# RADC-Microcontroller-S02-V00.net
KiCad netlist of a schematic drawn in Altium Designer
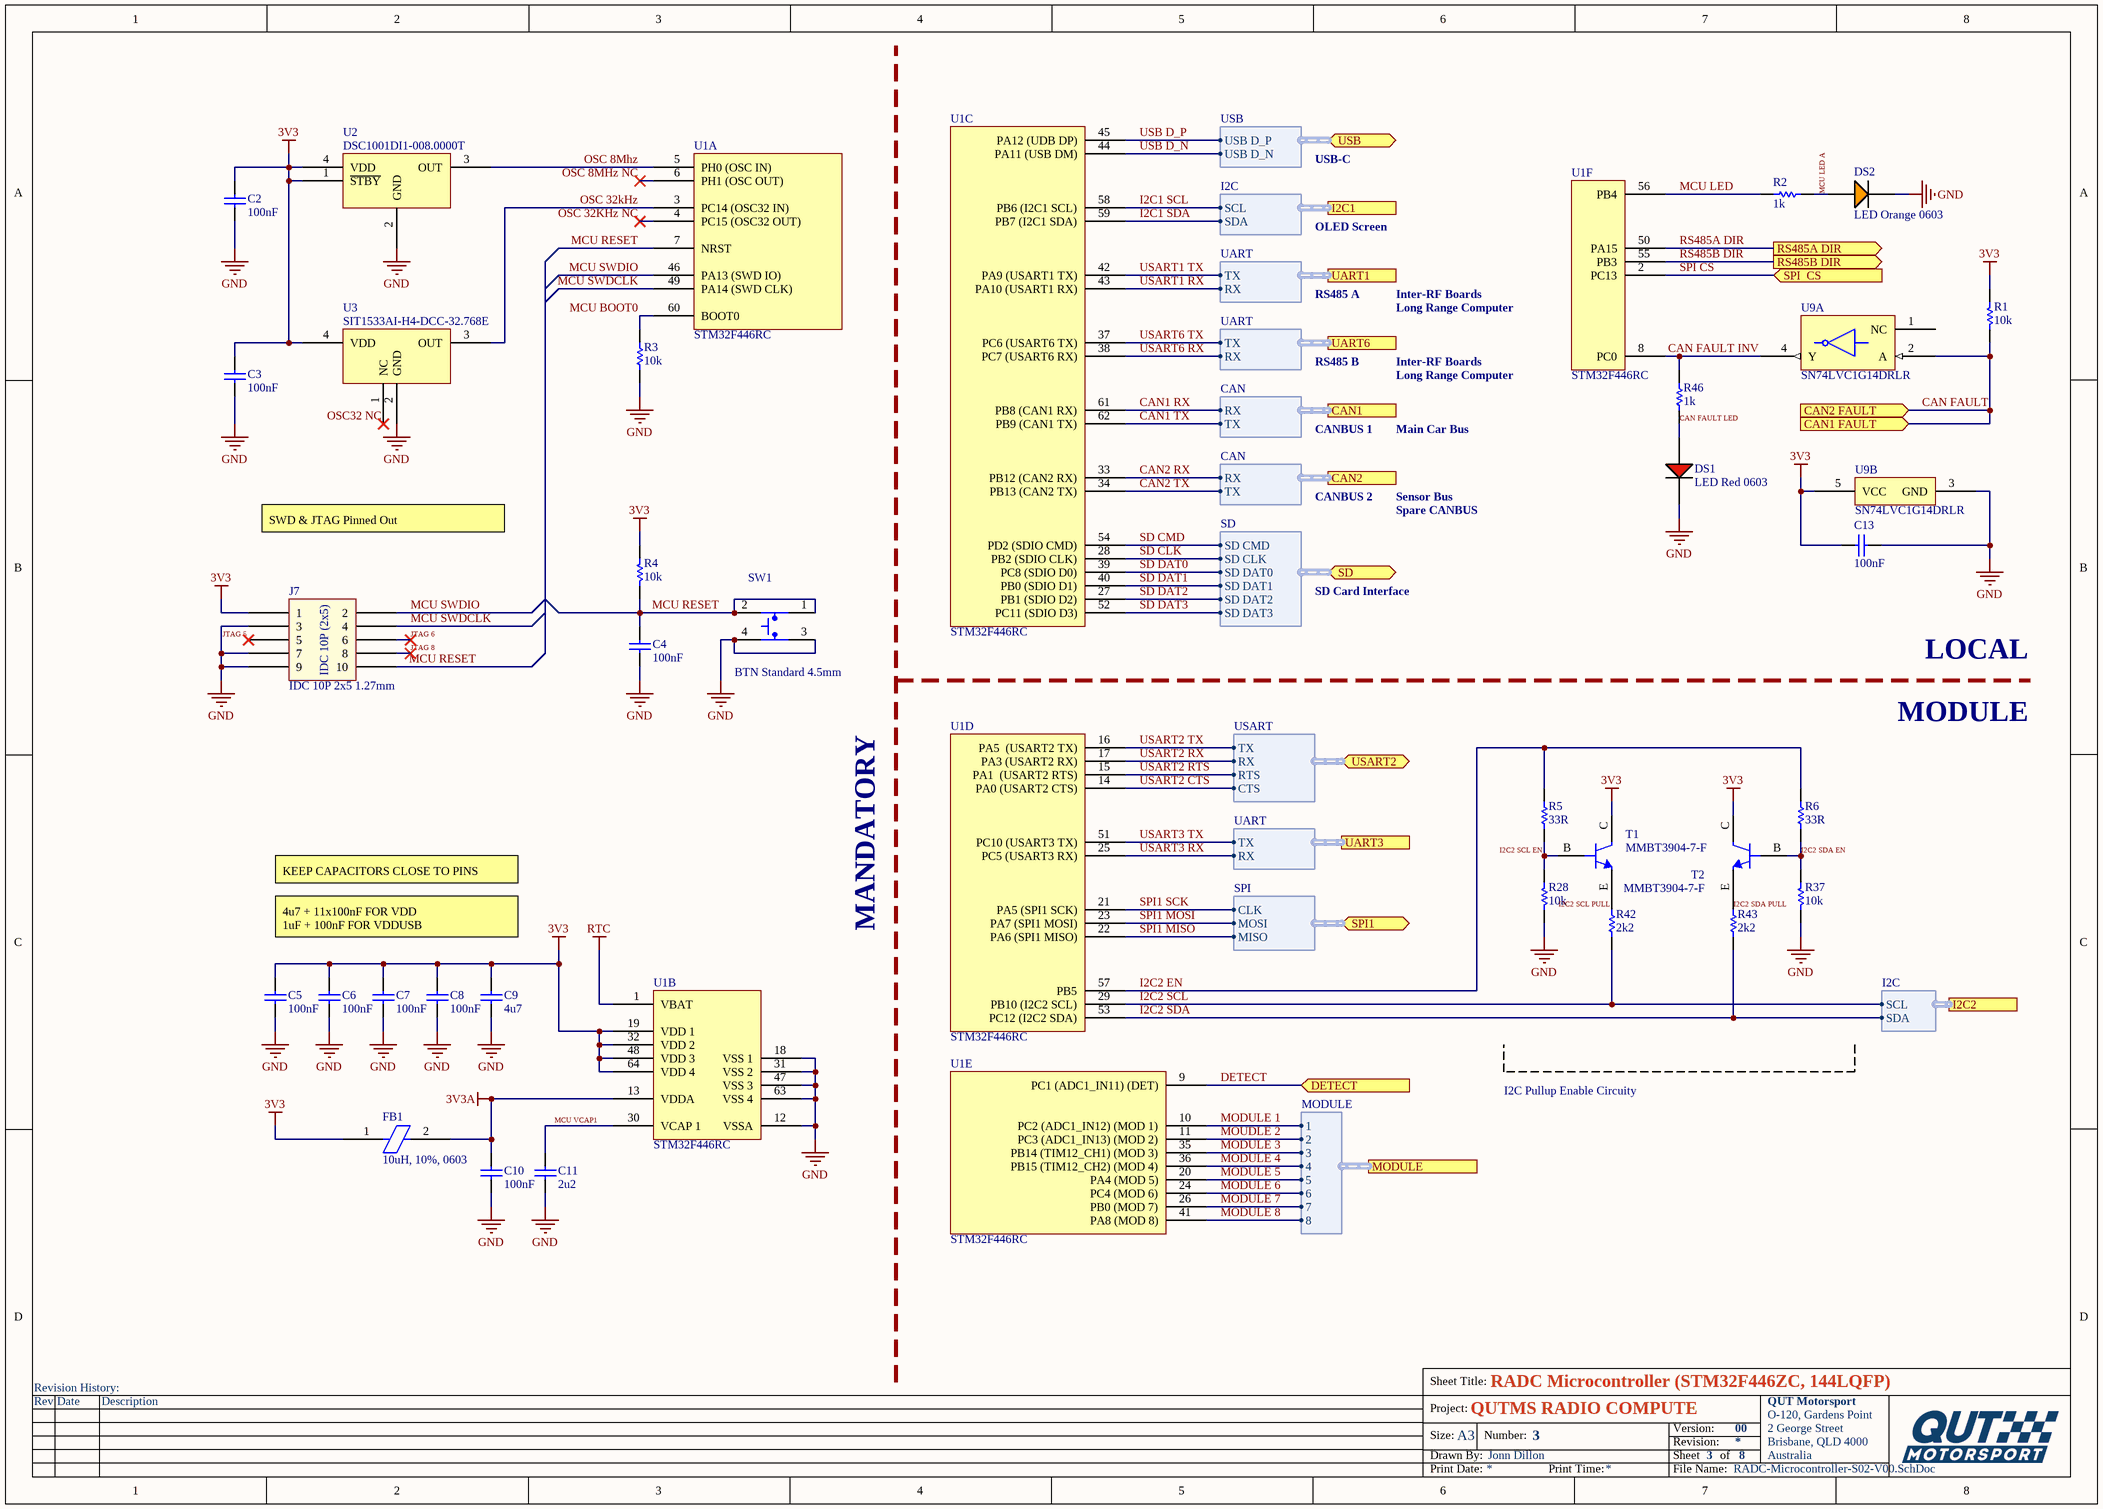
[diagram p0: RADC-Microcontroller-S02-V00.SchDoc]

(export (version "E")
  (design (tool "Eeschema 10.0.6"))
  (components
    (comp (ref "C2")
      (value "100nF")
      (footprint "Cap_Ceramic_0603")
      (description "Capacitor, Ceramic, SMD, 100nF, 50V, 5%, X7R, 0603")
      (libsource (lib "StandardCapacitors") (part "100nF 50V 5% X7R 0603"))
    )
    (comp (ref "C3")
      (value "100nF")
      (footprint "Cap_Ceramic_0603")
      (description "Capacitor, Ceramic, SMD, 100nF, 50V, 5%, X7R, 0603")
      (libsource (lib "StandardCapacitors") (part "100nF 50V 5% X7R 0603"))
    )
    (comp (ref "C4")
      (value "100nF")
      (footprint "Cap_Ceramic_0603")
      (description "Capacitor, Ceramic, SMD, 100nF, 50V, 5%, X7R, 0603")
      (libsource (lib "StandardCapacitors") (part "100nF 50V 5% X7R 0603"))
    )
    (comp (ref "C5")
      (value "100nF")
      (footprint "Cap_Ceramic_0603")
      (description "Capacitor, Ceramic, SMD, 100nF, 50V, 5%, X7R, 0603")
      (libsource (lib "StandardCapacitors") (part "100nF 50V 5% X7R 0603"))
    )
    (comp (ref "C6")
      (value "100nF")
      (footprint "Cap_Ceramic_0603")
      (description "Capacitor, Ceramic, SMD, 100nF, 50V, 5%, X7R, 0603")
      (libsource (lib "StandardCapacitors") (part "100nF 50V 5% X7R 0603"))
    )
    (comp (ref "C7")
      (value "100nF")
      (footprint "Cap_Ceramic_0603")
      (description "Capacitor, Ceramic, SMD, 100nF, 50V, 5%, X7R, 0603")
      (libsource (lib "StandardCapacitors") (part "100nF 50V 5% X7R 0603"))
    )
    (comp (ref "C8")
      (value "100nF")
      (footprint "Cap_Ceramic_0603")
      (description "Capacitor, Ceramic, SMD, 100nF, 50V, 5%, X7R, 0603")
      (libsource (lib "StandardCapacitors") (part "100nF 50V 5% X7R 0603"))
    )
    (comp (ref "C9")
      (value "4u7")
      (footprint "Cap_Ceramic_0603")
      (description "Capacitor, Ceramic, SMD, 4u7, 50V, 5%, X7R, 0603")
      (libsource (lib "StandardCapacitors") (part "4u7 50V 5% X7R 0603"))
    )
    (comp (ref "C10")
      (value "100nF")
      (footprint "Cap_Ceramic_0603")
      (description "Capacitor, Ceramic, SMD, 100nF, 50V, 5%, X7R, 0603")
      (libsource (lib "StandardCapacitors") (part "100nF 50V 5% X7R 0603"))
    )
    (comp (ref "C11")
      (value "2u2")
      (footprint "Cap_Ceramic_0603")
      (description "Capacitor, Ceramic, SMD, 2u2, 50V, 5%, X7R, 0603")
      (libsource (lib "StandardCapacitors") (part "2u2 50V 5% X7R 0603"))
    )
    (comp (ref "C13")
      (value "100nF")
      (footprint "Cap_Ceramic_0603")
      (description "Capacitor, Ceramic, SMD, 100nF, 50V, 5%, X7R, 0603")
      (libsource (lib "StandardCapacitors") (part "100nF 50V 5% X7R 0603"))
    )
    (comp (ref "DS1")
      (value "LED Red 0603")
      (footprint "LED RED 0603")
      (libsource (lib "QUTMS_LEDLibrary") (part "LED Red 0603"))
    )
    (comp (ref "DS2")
      (value "LED Orange 0603")
      (footprint "LED ORANGE 0603")
      (libsource (lib "QUTMS_LEDLibrary") (part "LED Orange 0603"))
    )
    (comp (ref "FB1")
      (value "10uH, 10%, 0603")
      (footprint "Inductor_0603")
      (libsource (lib "QUTMS_InductorLibrary") (part "10uH, 10%, 0603"))
    )
    (comp (ref "J7")
      (value "IDC 10P 2x5 1.27mm")
      (footprint "IDC 1.27MM 10P")
      (libsource (lib "QUTMS_IDCConnectors") (part "IDC 10P 2x5 1.27mm"))
    )
    (comp (ref "R1")
      (value "10k")
      (footprint "Res_ThinFilm_0603")
      (description "Resistor, SMD, 10k, 0.1W, 5%, 0603")
      (libsource (lib "StandardResistors") (part "10k 5% 0603"))
    )
    (comp (ref "R2")
      (value "1k")
      (footprint "Res_ThinFilm_0603")
      (description "Resistor, SMD, 1k, 0.1W, 5%, 0603")
      (libsource (lib "StandardResistors") (part "1k 5% 0603"))
    )
    (comp (ref "R3")
      (value "10k")
      (footprint "Res_ThinFilm_0603")
      (description "Resistor, SMD, 10k, 0.1W, 5%, 0603")
      (libsource (lib "StandardResistors") (part "10k 5% 0603"))
    )
    (comp (ref "R4")
      (value "10k")
      (footprint "Res_ThinFilm_0603")
      (description "Resistor, SMD, 10k, 0.1W, 5%, 0603")
      (libsource (lib "StandardResistors") (part "10k 5% 0603"))
    )
    (comp (ref "R5")
      (value "33R")
      (footprint "Res_ThinFilm_0603")
      (description "Resistor, SMD, 33R, 0.1W, 5%, 0603")
      (libsource (lib "StandardResistors") (part "33R 5% 0603"))
    )
    (comp (ref "R6")
      (value "33R")
      (footprint "Res_ThinFilm_0603")
      (description "Resistor, SMD, 33R, 0.1W, 5%, 0603")
      (libsource (lib "StandardResistors") (part "33R 5% 0603"))
    )
    (comp (ref "R28")
      (value "10k")
      (footprint "Res_ThinFilm_0603")
      (description "Resistor, SMD, 10k, 0.1W, 5%, 0603")
      (libsource (lib "StandardResistors") (part "10k 5% 0603"))
    )
    (comp (ref "R37")
      (value "10k")
      (footprint "Res_ThinFilm_0603")
      (description "Resistor, SMD, 10k, 0.1W, 5%, 0603")
      (libsource (lib "StandardResistors") (part "10k 5% 0603"))
    )
    (comp (ref "R42")
      (value "2k2")
      (footprint "Res_ThinFilm_0603")
      (description "Resistor, SMD, 2k2, 0.1W, 5%, 0603")
      (libsource (lib "StandardResistors") (part "2k2 5% 0603"))
    )
    (comp (ref "R43")
      (value "2k2")
      (footprint "Res_ThinFilm_0603")
      (description "Resistor, SMD, 2k2, 0.1W, 5%, 0603")
      (libsource (lib "StandardResistors") (part "2k2 5% 0603"))
    )
    (comp (ref "R46")
      (value "1k")
      (footprint "Res_ThinFilm_0603")
      (description "Resistor, SMD, 1k, 0.1W, 5%, 0603")
      (libsource (lib "StandardResistors") (part "1k 5% 0603"))
    )
    (comp (ref "SW1")
      (value "BTN Standard 4.5mm")
      (footprint "BTN STANDARD 4.5mm X 4.5mm")
      (description "Standard 4.5mm X 4.5mm momentary button")
      (libsource (lib "QUTMS_SwitchLibrary") (part "BTN Standard 4.5mm"))
    )
    (comp (ref "T1")
      (value "MMBT3904-7-F")
      (footprint "SOT23-3 - Transistor")
      (description "Bipolar (BJT) Transistor NPN 40V 200mA 300MHz 300mW Surface Mount SOT-23-3")
      (libsource (lib "QUTMS_MOSFETLibrary") (part "MMBT3904-7-F"))
    )
    (comp (ref "T2")
      (value "MMBT3904-7-F")
      (footprint "SOT23-3 - Transistor")
      (description "Bipolar (BJT) Transistor NPN 40V 200mA 300MHz 300mW Surface Mount SOT-23-3")
      (libsource (lib "QUTMS_MOSFETLibrary") (part "MMBT3904-7-F"))
    )
    (comp (ref "U1")
      (value "STM32F446RC")
      (footprint "STM-LQFP64_V")
      (description "ARM® Cortex®-M4 STM32F4 Microcontroller IC 32-Bit 180MHz 256KB (256K x 8) FLASH 64-LQFP (10x10)")
      (libsource (lib "QUTMS_STM32Library") (part "STM32F446RC"))
    )
    (comp (ref "U2")
      (value "DSC1001DI1-008.0000T")
      (footprint "DSC1001DI1-008.0000TCT-ND")
      (description "8MHz XO (Standard) CMOS Oscillator 1.8 ~ 3.3V Standby (Power Down) 4-SMD, No Lead")
      (libsource (lib "QUTMS_CrystalLibrary") (part "DSC1001DI1-008.0000T"))
    )
    (comp (ref "U3")
      (value "SIT1533AI-H4-DCC-32.768E")
      (footprint "SIT1533AI-H4-DCC-32.768E")
      (description "32.768kHz XO (Standard) LVCMOS Oscillator 1.5V ~ 3.63V 4-SMD, No Lead")
      (libsource (lib "QUTMS_CrystalLibrary") (part "SIT1533AI-H4-DCC-32.768E"))
    )
    (comp (ref "U9")
      (value "SN74LVC1G14DRLR")
      (footprint "SOT-553")
      (description "Inverter IC 1 Channel Schmitt Trigger SOT-5")
      (libsource (lib "QUTMS_IntegratedCircuitLibrary") (part "SN74LVC1G14DRLR"))
    )
  )
  (nets
    (net (code "9") (name "/CAN FAULT") (class "Default")
      (node (ref "R1") (pin "1") (pinfunction "1_1") (pintype "passive"))
      (node (ref "U9") (pin "2") (pinfunction "A_2") (pintype "input"))
    )
    (net (code "10") (name "/CAN FAULT INV") (class "Default")
      (node (ref "R46") (pin "2") (pinfunction "2_2") (pintype "passive"))
      (node (ref "U1") (pin "8") (pinfunction "PC0_8") (pintype "passive"))
      (node (ref "U9") (pin "4") (pinfunction "Y_4") (pintype "output"))
    )
    (net (code "11") (name "/CAN FAULT LED") (class "Default")
      (node (ref "DS1") (pin "1") (pinfunction "A_1") (pintype "passive"))
      (node (ref "R46") (pin "1") (pinfunction "1_1") (pintype "passive"))
    )
    (net (code "12") (name "/CAN1 RX") (class "Default")
      (node (ref "U1") (pin "61") (pinfunction "PB8_(CAN1_RX)_61") (pintype "passive"))
    )
    (net (code "13") (name "/CAN1 TX") (class "Default")
      (node (ref "U1") (pin "62") (pinfunction "PB9_(CAN1_TX)_62") (pintype "passive"))
    )
    (net (code "14") (name "/CAN2 RX") (class "Default")
      (node (ref "U1") (pin "33") (pinfunction "PB12_(CAN2_RX)_33") (pintype "passive"))
    )
    (net (code "15") (name "/CAN2 TX") (class "Default")
      (node (ref "U1") (pin "34") (pinfunction "PB13_(CAN2_TX)_34") (pintype "passive"))
    )
    (net (code "16") (name "/DETECT") (class "Default")
      (node (ref "U1") (pin "9") (pinfunction "PC1_(ADC1_IN11)_(DET)_9") (pintype "passive"))
    )
    (net (code "17") (name "/I2C1 SCL") (class "Default")
      (node (ref "U1") (pin "58") (pinfunction "PB6_(I2C1_SCL)_58") (pintype "passive"))
    )
    (net (code "18") (name "/I2C1 SDA") (class "Default")
      (node (ref "U1") (pin "59") (pinfunction "PB7_(I2C1_SDA)_59") (pintype "passive"))
    )
    (net (code "19") (name "/I2C2 EN") (class "Default")
      (node (ref "R5") (pin "2") (pinfunction "2_2") (pintype "passive"))
      (node (ref "R6") (pin "2") (pinfunction "2_2") (pintype "passive"))
      (node (ref "U1") (pin "57") (pinfunction "PB5_57") (pintype "passive"))
    )
    (net (code "20") (name "/I2C2 SCL") (class "Default")
      (node (ref "R42") (pin "1") (pinfunction "1_1") (pintype "passive"))
      (node (ref "U1") (pin "29") (pinfunction "PB10_(I2C2_SCL)_29") (pintype "passive"))
    )
    (net (code "21") (name "/I2C2 SCL EN") (class "Default")
      (node (ref "R28") (pin "2") (pinfunction "2_2") (pintype "passive"))
      (node (ref "R5") (pin "1") (pinfunction "1_1") (pintype "passive"))
      (node (ref "T1") (pin "B") (pinfunction "B_B") (pintype "passive"))
    )
    (net (code "23") (name "/I2C2 SDA") (class "Default")
      (node (ref "R43") (pin "1") (pinfunction "1_1") (pintype "passive"))
      (node (ref "U1") (pin "53") (pinfunction "PC12_(I2C2_SDA)_53") (pintype "passive"))
    )
    (net (code "24") (name "/I2C2 SDA EN") (class "Default")
      (node (ref "R37") (pin "2") (pinfunction "2_2") (pintype "passive"))
      (node (ref "R6") (pin "1") (pinfunction "1_1") (pintype "passive"))
      (node (ref "T2") (pin "B") (pinfunction "B_B") (pintype "passive"))
    )
    (net (code "26") (name "/JTAG 5") (class "Default")
      (node (ref "J7") (pin "5") (pinfunction "5_5") (pintype "passive+no_connect"))
    )
    (net (code "27") (name "/JTAG 6") (class "Default")
      (node (ref "J7") (pin "6") (pinfunction "6_6") (pintype "passive+no_connect"))
    )
    (net (code "28") (name "/JTAG 8") (class "Default")
      (node (ref "J7") (pin "8") (pinfunction "8_8") (pintype "passive+no_connect"))
    )
    (net (code "29") (name "/MCU BOOT0") (class "Default")
      (node (ref "R3") (pin "2") (pinfunction "2_2") (pintype "passive"))
      (node (ref "U1") (pin "60") (pinfunction "BOOT0_60") (pintype "passive"))
    )
    (net (code "30") (name "/MCU LED") (class "Default")
      (node (ref "R2") (pin "2") (pinfunction "2_2") (pintype "passive"))
      (node (ref "U1") (pin "56") (pinfunction "PB4_56") (pintype "passive"))
    )
    (net (code "31") (name "/MCU LED A") (class "Default")
      (node (ref "DS2") (pin "1") (pinfunction "A_1") (pintype "passive"))
      (node (ref "R2") (pin "1") (pinfunction "1_1") (pintype "passive"))
    )
    (net (code "32") (name "/MCU RESET") (class "Default")
      (node (ref "C4") (pin "2") (pinfunction "2_2") (pintype "passive"))
      (node (ref "J7") (pin "10") (pinfunction "10_10") (pintype "passive"))
      (node (ref "R4") (pin "1") (pinfunction "1_1") (pintype "passive"))
      (node (ref "SW1") (pin "1") (pinfunction "1_1") (pintype "passive"))
      (node (ref "SW1") (pin "2") (pinfunction "2_2") (pintype "passive"))
      (node (ref "U1") (pin "7") (pinfunction "NRST_7") (pintype "passive"))
    )
    (net (code "33") (name "/MCU SWDCLK") (class "Default")
      (node (ref "J7") (pin "4") (pinfunction "4_4") (pintype "passive"))
      (node (ref "U1") (pin "49") (pinfunction "PA14_(SWD_CLK)_49") (pintype "passive"))
    )
    (net (code "34") (name "/MCU SWDIO") (class "Default")
      (node (ref "J7") (pin "2") (pinfunction "2_2") (pintype "passive"))
      (node (ref "U1") (pin "46") (pinfunction "PA13_(SWD_IO)_46") (pintype "passive"))
    )
    (net (code "35") (name "/MCU VCAP1") (class "Default")
      (node (ref "C11") (pin "2") (pinfunction "2_2") (pintype "passive"))
      (node (ref "U1") (pin "30") (pinfunction "VCAP_1_30") (pintype "passive"))
    )
    (net (code "36") (name "/MODULE 1") (class "Default")
      (node (ref "U1") (pin "10") (pinfunction "PC2_(ADC1_IN12)_(MOD_1)_10") (pintype "passive"))
    )
    (net (code "37") (name "/MODULE 3") (class "Default")
      (node (ref "U1") (pin "35") (pinfunction "PB14_(TIM12_CH1)_(MOD_3)_35") (pintype "passive"))
    )
    (net (code "38") (name "/MODULE 4") (class "Default")
      (node (ref "U1") (pin "36") (pinfunction "PB15_(TIM12_CH2)_(MOD_4)_36") (pintype "passive"))
    )
    (net (code "39") (name "/MODULE 5") (class "Default")
      (node (ref "U1") (pin "20") (pinfunction "PA4_(MOD_5)_20") (pintype "passive"))
    )
    (net (code "40") (name "/MODULE 6") (class "Default")
      (node (ref "U1") (pin "24") (pinfunction "PC4_(MOD_6)_24") (pintype "passive"))
    )
    (net (code "41") (name "/MODULE 7") (class "Default")
      (node (ref "U1") (pin "26") (pinfunction "PB0_(MOD_7)_26") (pintype "passive"))
    )
    (net (code "42") (name "/MODULE 8") (class "Default")
      (node (ref "U1") (pin "41") (pinfunction "PA8_(MOD_8)_41") (pintype "passive"))
    )
    (net (code "43") (name "/MOUDLE 2") (class "Default")
      (node (ref "U1") (pin "11") (pinfunction "PC3_(ADC1_IN13)_(MOD_2)_11") (pintype "passive"))
    )
    (net (code "44") (name "/OSC 8MHz NC") (class "Default")
      (node (ref "U1") (pin "6") (pinfunction "PH1_(OSC_OUT)_6") (pintype "passive+no_connect"))
    )
    (net (code "45") (name "/OSC 8Mhz") (class "Default")
      (node (ref "U1") (pin "5") (pinfunction "PH0_(OSC_IN)_5") (pintype "passive"))
      (node (ref "U2") (pin "3") (pinfunction "OUT_3") (pintype "passive"))
    )
    (net (code "46") (name "/OSC 32KHz NC") (class "Default")
      (node (ref "U1") (pin "4") (pinfunction "PC15_(OSC32_OUT)_4") (pintype "passive+no_connect"))
    )
    (net (code "47") (name "/OSC 32kHz") (class "Default")
      (node (ref "U1") (pin "3") (pinfunction "PC14_(OSC32_IN)_3") (pintype "passive"))
      (node (ref "U3") (pin "3") (pinfunction "OUT_3") (pintype "passive"))
    )
    (net (code "48") (name "/OSC32 NC") (class "Default")
      (node (ref "U3") (pin "1") (pinfunction "NC_1") (pintype "passive+no_connect"))
    )
    (net (code "49") (name "/RS485A DIR") (class "Default")
      (node (ref "U1") (pin "50") (pinfunction "PA15_50") (pintype "passive"))
    )
    (net (code "50") (name "/RS485B DIR") (class "Default")
      (node (ref "U1") (pin "55") (pinfunction "PB3_55") (pintype "passive"))
    )
    (net (code "51") (name "/SD CLK") (class "Default")
      (node (ref "U1") (pin "28") (pinfunction "PB2_(SDIO_CLK)_28") (pintype "passive"))
    )
    (net (code "52") (name "/SD CMD") (class "Default")
      (node (ref "U1") (pin "54") (pinfunction "PD2_(SDIO_CMD)_54") (pintype "passive"))
    )
    (net (code "53") (name "/SD DAT0") (class "Default")
      (node (ref "U1") (pin "39") (pinfunction "PC8_(SDIO_D0)_39") (pintype "passive"))
    )
    (net (code "54") (name "/SD DAT1") (class "Default")
      (node (ref "U1") (pin "40") (pinfunction "PB0_(SDIO_D1)_40") (pintype "passive"))
    )
    (net (code "55") (name "/SD DAT2") (class "Default")
      (node (ref "U1") (pin "27") (pinfunction "PB1_(SDIO_D2)_27") (pintype "passive"))
    )
    (net (code "56") (name "/SD DAT3") (class "Default")
      (node (ref "U1") (pin "52") (pinfunction "PC11_(SDIO_D3)_52") (pintype "passive"))
    )
    (net (code "57") (name "/SPI CS") (class "Default")
      (node (ref "U1") (pin "2") (pinfunction "PC13_2") (pintype "passive"))
    )
    (net (code "58") (name "/SPI1 MISO") (class "Default")
      (node (ref "U1") (pin "22") (pinfunction "PA6_(SPI1_MISO)_22") (pintype "passive"))
    )
    (net (code "59") (name "/SPI1 MOSI") (class "Default")
      (node (ref "U1") (pin "23") (pinfunction "PA7_(SPI1_MOSI)_23") (pintype "passive"))
    )
    (net (code "60") (name "/SPI1 SCK") (class "Default")
      (node (ref "U1") (pin "21") (pinfunction "PA5_(SPI1_SCK)_21") (pintype "passive"))
    )
    (net (code "61") (name "/USART1 RX") (class "Default")
      (node (ref "U1") (pin "43") (pinfunction "PA10_(USART1_RX)_43") (pintype "passive"))
    )
    (net (code "62") (name "/USART1 TX") (class "Default")
      (node (ref "U1") (pin "42") (pinfunction "PA9_(USART1_TX)_42") (pintype "passive"))
    )
    (net (code "63") (name "/USART2 CTS") (class "Default")
      (node (ref "U1") (pin "14") (pinfunction "PA0_(USART2_CTS)_14") (pintype "passive"))
    )
    (net (code "64") (name "/USART2 RTS") (class "Default")
      (node (ref "U1") (pin "15") (pinfunction "PA1__(USART2_RTS)_15") (pintype "passive"))
    )
    (net (code "65") (name "/USART2 RX") (class "Default")
      (node (ref "U1") (pin "17") (pinfunction "PA3_(USART2_RX)_17") (pintype "passive"))
    )
    (net (code "66") (name "/USART2 TX") (class "Default")
      (node (ref "U1") (pin "16") (pinfunction "PA5__(USART2_TX)_16") (pintype "passive"))
    )
    (net (code "67") (name "/USART3 RX") (class "Default")
      (node (ref "U1") (pin "25") (pinfunction "PC5_(USART3_RX)_25") (pintype "passive"))
    )
    (net (code "68") (name "/USART3 TX") (class "Default")
      (node (ref "U1") (pin "51") (pinfunction "PC10_(USART3_TX)_51") (pintype "passive"))
    )
    (net (code "69") (name "/USART6 RX") (class "Default")
      (node (ref "U1") (pin "38") (pinfunction "PC7_(USART6_RX)_38") (pintype "passive"))
    )
    (net (code "70") (name "/USART6 TX") (class "Default")
      (node (ref "U1") (pin "37") (pinfunction "PC6_(USART6_TX)_37") (pintype "passive"))
    )
    (net (code "71") (name "/USB D_N") (class "Default")
      (node (ref "U1") (pin "44") (pinfunction "PA11_(USB_DM)_44") (pintype "passive"))
    )
    (net (code "72") (name "/USB D_P") (class "Default")
      (node (ref "U1") (pin "45") (pinfunction "PA12_(UDB_DP)_45") (pintype "passive"))
    )
    (net (code "81") (name "3V3") (class "Default")
      (node (ref "C13") (pin "2") (pinfunction "2_2") (pintype "passive"))
      (node (ref "C2") (pin "2") (pinfunction "2_2") (pintype "passive"))
      (node (ref "C3") (pin "2") (pinfunction "2_2") (pintype "passive"))
      (node (ref "C5") (pin "2") (pinfunction "2_2") (pintype "passive"))
      (node (ref "C6") (pin "2") (pinfunction "2_2") (pintype "passive"))
      (node (ref "C7") (pin "2") (pinfunction "2_2") (pintype "passive"))
      (node (ref "C8") (pin "2") (pinfunction "2_2") (pintype "passive"))
      (node (ref "C9") (pin "2") (pinfunction "2_2") (pintype "passive"))
      (node (ref "FB1") (pin "1") (pinfunction "1_1") (pintype "passive"))
      (node (ref "J7") (pin "1") (pinfunction "1_1") (pintype "passive"))
      (node (ref "R1") (pin "2") (pinfunction "2_2") (pintype "passive"))
      (node (ref "R4") (pin "2") (pinfunction "2_2") (pintype "passive"))
      (node (ref "T1") (pin "C") (pinfunction "C_C") (pintype "passive"))
      (node (ref "T2") (pin "C") (pinfunction "C_C") (pintype "passive"))
      (node (ref "U1") (pin "19") (pinfunction "VDD_1_19") (pintype "passive"))
      (node (ref "U1") (pin "32") (pinfunction "VDD_2_32") (pintype "passive"))
      (node (ref "U1") (pin "48") (pinfunction "VDD_3_48") (pintype "passive"))
      (node (ref "U1") (pin "64") (pinfunction "VDD_4_64") (pintype "passive"))
      (node (ref "U2") (pin "1") (pinfunction "~{STBY}_1") (pintype "passive"))
      (node (ref "U2") (pin "4") (pinfunction "VDD_4") (pintype "passive"))
      (node (ref "U3") (pin "4") (pinfunction "VDD_4") (pintype "passive"))
      (node (ref "U9") (pin "5") (pinfunction "VCC_5") (pintype "passive"))
    )
    (net (code "82") (name "3V3A") (class "Default")
      (node (ref "C10") (pin "2") (pinfunction "2_2") (pintype "passive"))
      (node (ref "FB1") (pin "2") (pinfunction "2_2") (pintype "passive"))
      (node (ref "U1") (pin "13") (pinfunction "VDDA_13") (pintype "passive"))
    )
    (net (code "83") (name "GND") (class "Default")
      (node (ref "C10") (pin "1") (pinfunction "1_1") (pintype "passive"))
      (node (ref "C11") (pin "1") (pinfunction "1_1") (pintype "passive"))
      (node (ref "C13") (pin "1") (pinfunction "1_1") (pintype "passive"))
      (node (ref "C2") (pin "1") (pinfunction "1_1") (pintype "passive"))
      (node (ref "C3") (pin "1") (pinfunction "1_1") (pintype "passive"))
      (node (ref "C4") (pin "1") (pinfunction "1_1") (pintype "passive"))
      (node (ref "C5") (pin "1") (pinfunction "1_1") (pintype "passive"))
      (node (ref "C6") (pin "1") (pinfunction "1_1") (pintype "passive"))
      (node (ref "C7") (pin "1") (pinfunction "1_1") (pintype "passive"))
      (node (ref "C8") (pin "1") (pinfunction "1_1") (pintype "passive"))
      (node (ref "C9") (pin "1") (pinfunction "1_1") (pintype "passive"))
      (node (ref "DS1") (pin "2") (pinfunction "C_2") (pintype "passive"))
      (node (ref "DS2") (pin "2") (pinfunction "C_2") (pintype "passive"))
      (node (ref "J7") (pin "3") (pinfunction "3_3") (pintype "passive"))
      (node (ref "J7") (pin "7") (pinfunction "7_7") (pintype "passive"))
      (node (ref "J7") (pin "9") (pinfunction "9_9") (pintype "passive"))
      (node (ref "R28") (pin "1") (pinfunction "1_1") (pintype "passive"))
      (node (ref "R3") (pin "1") (pinfunction "1_1") (pintype "passive"))
      (node (ref "R37") (pin "1") (pinfunction "1_1") (pintype "passive"))
      (node (ref "SW1") (pin "3") (pinfunction "3_3") (pintype "passive"))
      (node (ref "SW1") (pin "4") (pinfunction "4_4") (pintype "passive"))
      (node (ref "U1") (pin "12") (pinfunction "VSSA_12") (pintype "passive"))
      (node (ref "U1") (pin "18") (pinfunction "VSS_1_18") (pintype "passive"))
      (node (ref "U1") (pin "31") (pinfunction "VSS_2_31") (pintype "passive"))
      (node (ref "U1") (pin "47") (pinfunction "VSS_3_47") (pintype "passive"))
      (node (ref "U1") (pin "63") (pinfunction "VSS_4_63") (pintype "passive"))
      (node (ref "U2") (pin "2") (pinfunction "GND_2") (pintype "passive"))
      (node (ref "U3") (pin "2") (pinfunction "GND_2") (pintype "passive"))
      (node (ref "U9") (pin "3") (pinfunction "GND_3") (pintype "passive"))
    )
    (net (code "84") (name "Net-(R42-Pad2)") (class "Default")
      (node (ref "R42") (pin "2") (pinfunction "2_2") (pintype "passive"))
      (node (ref "T1") (pin "E") (pinfunction "E_E") (pintype "passive"))
    )
    (net (code "85") (name "Net-(R43-Pad2)") (class "Default")
      (node (ref "R43") (pin "2") (pinfunction "2_2") (pintype "passive"))
      (node (ref "T2") (pin "E") (pinfunction "E_E") (pintype "passive"))
    )
    (net (code "86") (name "RTC") (class "Default")
      (node (ref "U1") (pin "1") (pinfunction "VBAT_1") (pintype "passive"))
    )
    (net (code "87") (name "unconnected-(U9A-NC-Pad1)") (class "Default")
      (node (ref "U9") (pin "1") (pinfunction "NC_1") (pintype "passive"))
    )
  )
)
